# homecomputer-6502_5.net
KiCad netlist of a schematic drawn in Altium Designer
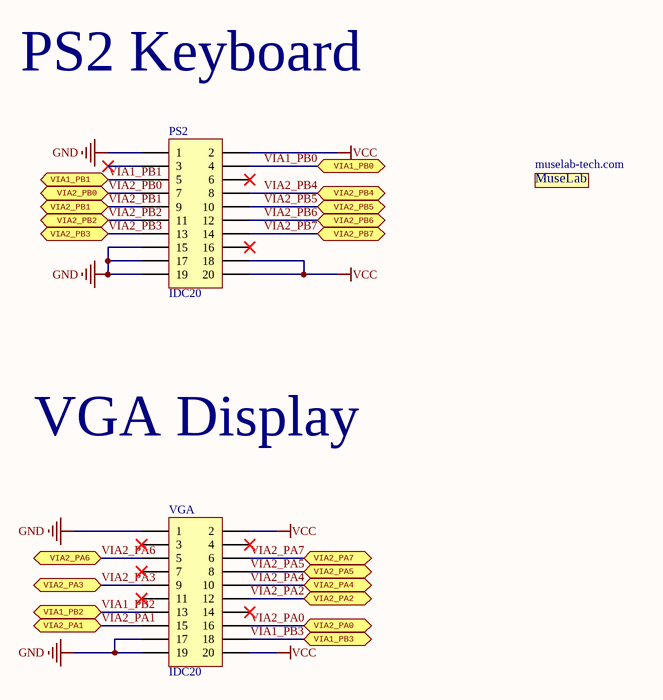
[diagram p0: homecomputer-6502_5.SchDoc]

(export (version "E")
  (design (tool "Eeschema 10.0.6"))
  (components
    (comp (ref "muselab-tech.com")
      (value "LOGO_MuseLab")
      (footprint "LOGO_MUSELAB")
      (libsource (lib "homecomputer-6502") (part "LOGO_MuseLab"))
    )
    (comp (ref "PS2") (value "IDC20") (footprint "IDC20") (libsource (lib "stm8") (part "IDC20")))
    (comp (ref "VGA") (value "IDC20") (footprint "IDC20") (libsource (lib "nanoDAP") (part "IDC20")))
  )
  (nets
    (net (code "1") (name "/VIA1_PB0") (class "Default")
      (node (ref "PS2") (pin "4") (pinfunction "4_4") (pintype "passive"))
    )
    (net (code "2") (name "/VIA1_PB1") (class "Default")
      (node (ref "PS2") (pin "5") (pinfunction "5_5") (pintype "passive"))
    )
    (net (code "3") (name "/VIA1_PB2") (class "Default")
      (node (ref "VGA") (pin "13") (pinfunction "13_13") (pintype "passive"))
    )
    (net (code "4") (name "/VIA1_PB3") (class "Default")
      (node (ref "VGA") (pin "18") (pinfunction "18_18") (pintype "passive"))
    )
    (net (code "5") (name "/VIA2_PA0") (class "Default")
      (node (ref "VGA") (pin "16") (pinfunction "16_16") (pintype "passive"))
    )
    (net (code "6") (name "/VIA2_PA1") (class "Default")
      (node (ref "VGA") (pin "15") (pinfunction "15_15") (pintype "passive"))
    )
    (net (code "7") (name "/VIA2_PA2") (class "Default")
      (node (ref "VGA") (pin "12") (pinfunction "12_12") (pintype "passive"))
    )
    (net (code "8") (name "/VIA2_PA3") (class "Default")
      (node (ref "VGA") (pin "9") (pinfunction "9_9") (pintype "passive"))
    )
    (net (code "9") (name "/VIA2_PA4") (class "Default")
      (node (ref "VGA") (pin "10") (pinfunction "10_10") (pintype "passive"))
    )
    (net (code "10") (name "/VIA2_PA5") (class "Default")
      (node (ref "VGA") (pin "8") (pinfunction "8_8") (pintype "passive"))
    )
    (net (code "11") (name "/VIA2_PA6") (class "Default")
      (node (ref "VGA") (pin "5") (pinfunction "5_5") (pintype "passive"))
    )
    (net (code "12") (name "/VIA2_PA7") (class "Default")
      (node (ref "VGA") (pin "6") (pinfunction "6_6") (pintype "passive"))
    )
    (net (code "13") (name "/VIA2_PB0") (class "Default")
      (node (ref "PS2") (pin "7") (pinfunction "7_7") (pintype "passive"))
    )
    (net (code "14") (name "/VIA2_PB1") (class "Default")
      (node (ref "PS2") (pin "9") (pinfunction "9_9") (pintype "passive"))
    )
    (net (code "15") (name "/VIA2_PB2") (class "Default")
      (node (ref "PS2") (pin "11") (pinfunction "11_11") (pintype "passive"))
    )
    (net (code "16") (name "/VIA2_PB3") (class "Default")
      (node (ref "PS2") (pin "13") (pinfunction "13_13") (pintype "passive"))
    )
    (net (code "17") (name "/VIA2_PB4") (class "Default")
      (node (ref "PS2") (pin "8") (pinfunction "8_8") (pintype "passive"))
    )
    (net (code "18") (name "/VIA2_PB5") (class "Default")
      (node (ref "PS2") (pin "10") (pinfunction "10_10") (pintype "passive"))
    )
    (net (code "19") (name "/VIA2_PB6") (class "Default")
      (node (ref "PS2") (pin "12") (pinfunction "12_12") (pintype "passive"))
    )
    (net (code "20") (name "/VIA2_PB7") (class "Default")
      (node (ref "PS2") (pin "14") (pinfunction "14_14") (pintype "passive"))
    )
    (net (code "21") (name "GND") (class "Default")
      (node (ref "PS2") (pin "1") (pinfunction "1_1") (pintype "passive"))
      (node (ref "PS2") (pin "15") (pinfunction "15_15") (pintype "passive"))
      (node (ref "PS2") (pin "17") (pinfunction "17_17") (pintype "passive"))
      (node (ref "PS2") (pin "19") (pinfunction "19_19") (pintype "passive"))
      (node (ref "VGA") (pin "1") (pinfunction "1_1") (pintype "passive"))
      (node (ref "VGA") (pin "17") (pinfunction "17_17") (pintype "passive"))
      (node (ref "VGA") (pin "19") (pinfunction "19_19") (pintype "passive"))
    )
    (net (code "22") (name "VCC") (class "Default")
      (node (ref "PS2") (pin "18") (pinfunction "18_18") (pintype "passive"))
      (node (ref "PS2") (pin "2") (pinfunction "2_2") (pintype "passive"))
      (node (ref "PS2") (pin "20") (pinfunction "20_20") (pintype "passive"))
      (node (ref "VGA") (pin "2") (pinfunction "2_2") (pintype "passive"))
      (node (ref "VGA") (pin "20") (pinfunction "20_20") (pintype "passive"))
    )
    (net (code "23") (name "unconnected-(PS2-Pad3)") (class "Default")
      (node (ref "PS2") (pin "3") (pinfunction "3_3") (pintype "passive+no_connect"))
    )
    (net (code "24") (name "unconnected-(PS2-Pad6)") (class "Default")
      (node (ref "PS2") (pin "6") (pinfunction "6_6") (pintype "passive+no_connect"))
    )
    (net (code "25") (name "unconnected-(PS2-Pad16)") (class "Default")
      (node (ref "PS2") (pin "16") (pinfunction "16_16") (pintype "passive+no_connect"))
    )
    (net (code "26") (name "unconnected-(VGA-Pad3)") (class "Default")
      (node (ref "VGA") (pin "3") (pinfunction "3_3") (pintype "passive+no_connect"))
    )
    (net (code "27") (name "unconnected-(VGA-Pad4)") (class "Default")
      (node (ref "VGA") (pin "4") (pinfunction "4_4") (pintype "passive+no_connect"))
    )
    (net (code "28") (name "unconnected-(VGA-Pad7)") (class "Default")
      (node (ref "VGA") (pin "7") (pinfunction "7_7") (pintype "passive+no_connect"))
    )
    (net (code "29") (name "unconnected-(VGA-Pad11)") (class "Default")
      (node (ref "VGA") (pin "11") (pinfunction "11_11") (pintype "passive+no_connect"))
    )
    (net (code "30") (name "unconnected-(VGA-Pad14)") (class "Default")
      (node (ref "VGA") (pin "14") (pinfunction "14_14") (pintype "passive+no_connect"))
    )
  )
)
